# Power.net
KiCad netlist of a schematic drawn in Altium Designer
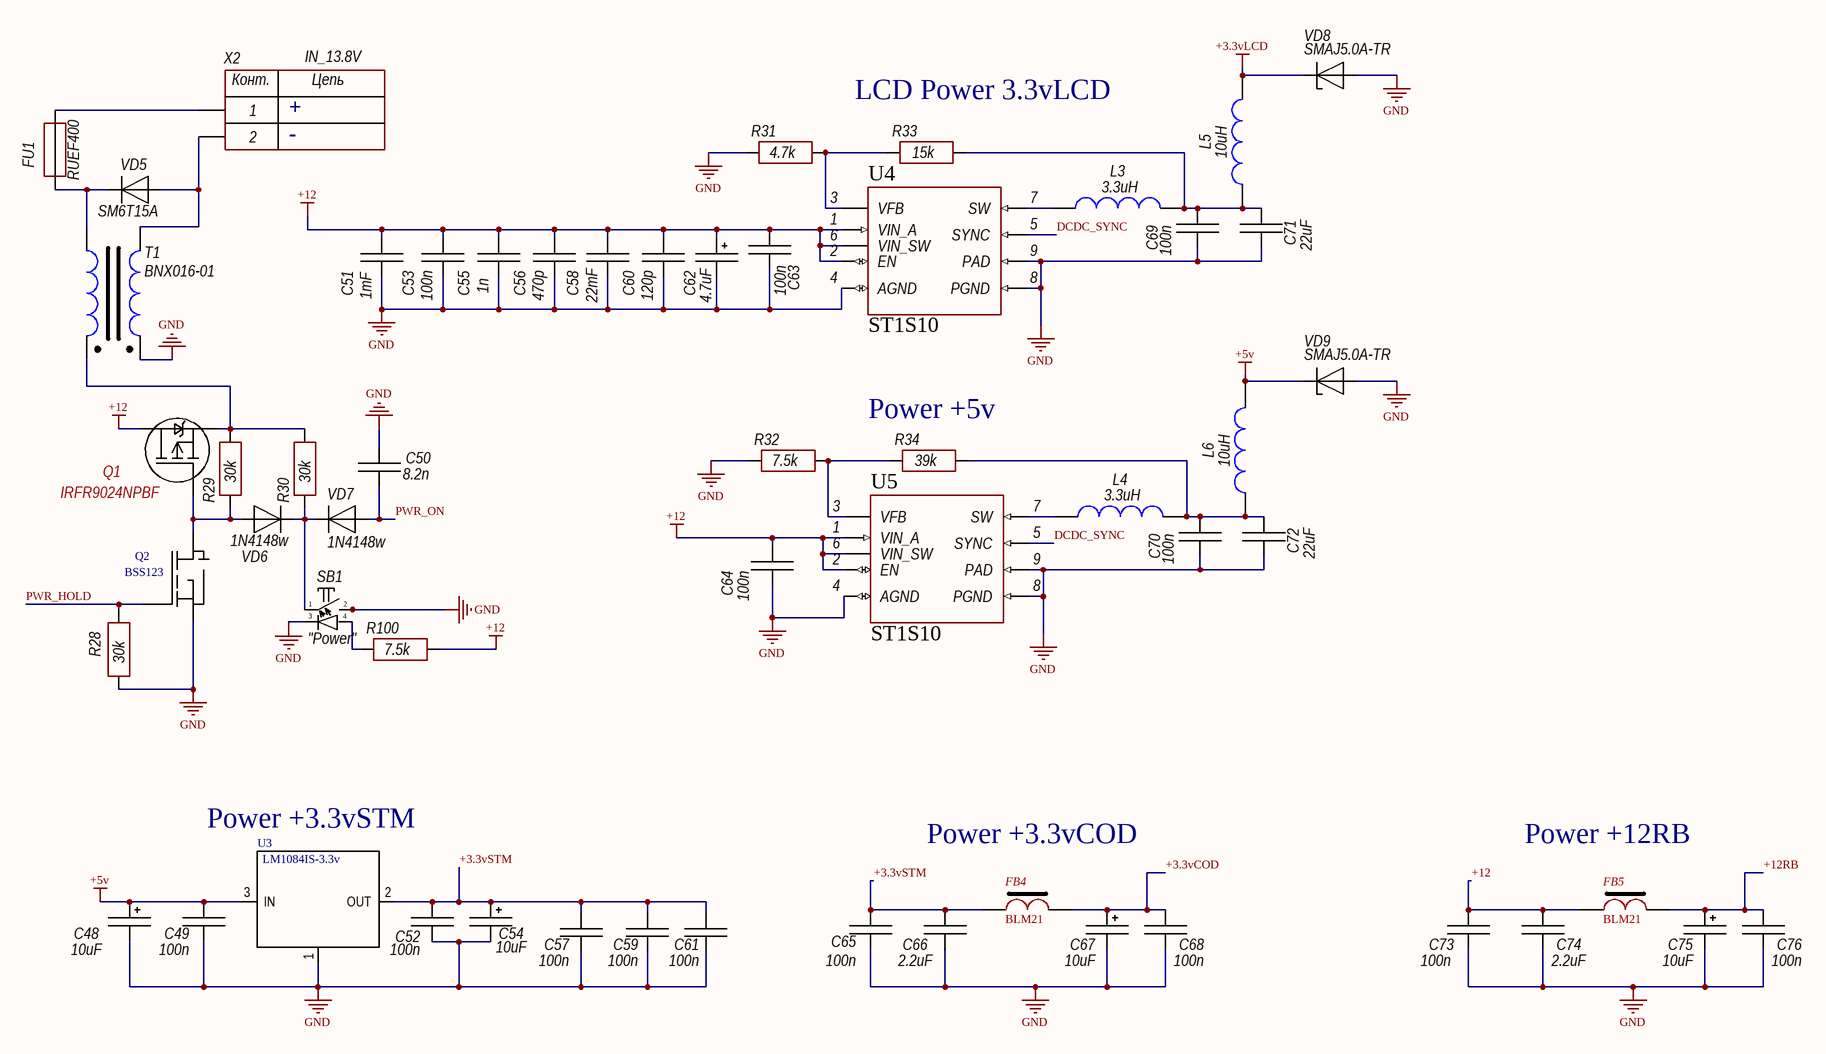
[diagram p0: Power.SchDoc]

(export (version "E")
  (design (tool "Eeschema 10.0.6"))
  (components
    (comp (ref "C48")
      (value "10uF")
      (footprint "standard:TANTAL_B")
      (libsource (lib "Discrete") (part "TantalCap"))
    )
    (comp (ref "C49")
      (value "100n")
      (footprint "standard:CH0805C")
      (libsource (lib "Discrete") (part "Capacitor"))
    )
    (comp (ref "C50")
      (value "8.2n")
      (footprint "standard:CH0805C")
      (libsource (lib "Discrete") (part "Capacitor"))
    )
    (comp (ref "C51")
      (value "1mF")
      (footprint "standard:CH0805C")
      (libsource (lib "Discrete") (part "Capacitor"))
    )
    (comp (ref "C52")
      (value "100n")
      (footprint "standard:CH0805C")
      (libsource (lib "Discrete") (part "Capacitor"))
    )
    (comp (ref "C53")
      (value "100n")
      (footprint "standard:CH0805C")
      (libsource (lib "Discrete") (part "Capacitor"))
    )
    (comp (ref "C54")
      (value "10uF")
      (footprint "standard:TANTAL_B")
      (libsource (lib "Discrete") (part "TantalCap"))
    )
    (comp (ref "C55")
      (value "1n")
      (footprint "standard:CH0805C")
      (libsource (lib "Discrete") (part "Capacitor"))
    )
    (comp (ref "C56")
      (value "470p")
      (footprint "standard:CH0805C")
      (libsource (lib "Discrete") (part "Capacitor"))
    )
    (comp (ref "C57")
      (value "100n")
      (footprint "standard:CH0805C")
      (libsource (lib "Discrete") (part "Capacitor"))
    )
    (comp (ref "C58")
      (value "22mF")
      (footprint "standard:CH1210C")
      (libsource (lib "Discrete") (part "Capacitor"))
    )
    (comp (ref "C59")
      (value "100n")
      (footprint "standard:CH0805C")
      (libsource (lib "Discrete") (part "Capacitor"))
    )
    (comp (ref "C60")
      (value "120p")
      (footprint "standard:CH0805C")
      (libsource (lib "Discrete") (part "Capacitor"))
    )
    (comp (ref "C61")
      (value "100n")
      (footprint "standard:CH0805C")
      (libsource (lib "Discrete") (part "Capacitor"))
    )
    (comp (ref "C62")
      (value "4.7uF")
      (footprint "standard:D6.3C2.5H11")
      (libsource (lib "Discrete") (part "AlumCap"))
    )
    (comp (ref "C63")
      (value "100n")
      (footprint "standard:CH0805C")
      (libsource (lib "Discrete") (part "Capacitor"))
    )
    (comp (ref "C64")
      (value "100n")
      (footprint "standard:CH0805C")
      (libsource (lib "Discrete") (part "Capacitor"))
    )
    (comp (ref "C65")
      (value "100n")
      (footprint "standard:CH0805C")
      (libsource (lib "Discrete") (part "Capacitor"))
    )
    (comp (ref "C66")
      (value "2.2uF")
      (footprint "standard:CH0805C")
      (libsource (lib "Discrete") (part "Capacitor"))
    )
    (comp (ref "C67")
      (value "10uF")
      (footprint "standard:TANTAL_B")
      (libsource (lib "Discrete") (part "TantalCap"))
    )
    (comp (ref "C68")
      (value "100n")
      (footprint "standard:CH0805C")
      (libsource (lib "Discrete") (part "Capacitor"))
    )
    (comp (ref "C69")
      (value "100n")
      (footprint "standard:CH0805C")
      (libsource (lib "Discrete") (part "Capacitor"))
    )
    (comp (ref "C70")
      (value "100n")
      (footprint "standard:CH0805C")
      (libsource (lib "Discrete") (part "Capacitor"))
    )
    (comp (ref "C71")
      (value "22uF")
      (footprint "standard:CH1210C")
      (libsource (lib "Discrete") (part "Capacitor"))
    )
    (comp (ref "C72")
      (value "22uF")
      (footprint "standard:CH1210C")
      (libsource (lib "Discrete") (part "Capacitor"))
    )
    (comp (ref "C73")
      (value "100n")
      (footprint "standard:CH0805C")
      (libsource (lib "Discrete") (part "Capacitor"))
    )
    (comp (ref "C74")
      (value "2.2uF")
      (footprint "standard:CH0805C")
      (libsource (lib "Discrete") (part "Capacitor"))
    )
    (comp (ref "C75")
      (value "10uF")
      (footprint "standard:TANTAL_B")
      (libsource (lib "Discrete") (part "TantalCap"))
    )
    (comp (ref "C76")
      (value "100n")
      (footprint "standard:CH0805C")
      (libsource (lib "Discrete") (part "Capacitor"))
    )
    (comp (ref "FB4") (value "BLM21") (footprint "CH0805L") (libsource (lib "Discrete") (part "FB-1")))
    (comp (ref "FB5") (value "BLM21") (footprint "CH0805L") (libsource (lib "Discrete") (part "FB-1")))
    (comp (ref "FU1")
      (value "RUEF400")
      (footprint "Fuse: Ruef400")
      (libsource (lib "Discrete") (part "Fuse"))
    )
    (comp (ref "L3")
      (value "3.3uH")
      (footprint "custom:IND: CDRH74")
      (libsource (lib "Discrete") (part "Inductor"))
    )
    (comp (ref "L4")
      (value "3.3uH")
      (footprint "custom:IND: CDRH127")
      (libsource (lib "Discrete") (part "Inductor"))
    )
    (comp (ref "L5")
      (value "10uH")
      (footprint "custom:IND: CDRH74")
      (libsource (lib "Discrete") (part "Inductor"))
    )
    (comp (ref "L6")
      (value "10uH")
      (footprint "custom:IND: CDRH74")
      (libsource (lib "Discrete") (part "Inductor"))
    )
    (comp (ref "Q1")
      (value "IRFR9024NPBF")
      (footprint "D2PAK_132")
      (libsource (lib "Transistor") (part "P-KANAL"))
    )
    (comp (ref "Q2") (value "BSS123") (footprint "SOT23_132") (libsource (lib "Transistor") (part "BSS123")))
    (comp (ref "R28") (value "30k") (footprint "standard:CH0805R") (libsource (lib "") (part "Resistor_1")))
    (comp (ref "R29") (value "30k") (footprint "standard:CH0805R") (libsource (lib "") (part "Resistor_1")))
    (comp (ref "R30") (value "30k") (footprint "standard:CH0805R") (libsource (lib "") (part "Resistor_1")))
    (comp (ref "R31")
      (value "4.7k")
      (footprint "standard:CH0805R")
      (libsource (lib "Discrete") (part "Resistor"))
    )
    (comp (ref "R32")
      (value "7.5k")
      (footprint "standard:CH0805R")
      (libsource (lib "Discrete") (part "Resistor"))
    )
    (comp (ref "R33")
      (value "15k")
      (footprint "standard:CH0805R")
      (libsource (lib "Discrete") (part "Resistor"))
    )
    (comp (ref "R34")
      (value "39k")
      (footprint "standard:CH0805R")
      (libsource (lib "Discrete") (part "Resistor"))
    )
    (comp (ref "R100")
      (value "7.5k")
      (footprint "standard:CH0805R")
      (libsource (lib "Discrete") (part "Resistor"))
    )
    (comp (ref "SB1")
      (value "\"Power\"")
      (footprint "BUT: 6x6 LED")
      (description "6x6 mm")
      (libsource (lib "Connectors") (part "Tactile switches_LED"))
    )
    (comp (ref "T1")
      (value "BNX016-01")
      (footprint "BNX016-01")
      (fields (field (name "MANUFACTURER") "Murata Electronics North America"))
      (libsource (lib "Transformers") (part "EMI bead"))
    )
    (comp (ref "U3")
      (value "LM1084IS-3.3v")
      (footprint "TO-263-3(123)")
      (libsource (lib "Power Supplies") (part "LM1084"))
    )
    (comp (ref "U4") (value "ST1S10") (footprint "8-SOIC (PAD)") (libsource (lib "Digital") (part "ST1S10")))
    (comp (ref "U5") (value "ST1S10") (footprint "8-SOIC (PAD)") (libsource (lib "Digital") (part "ST1S10")))
    (comp (ref "VD5") (value "SM6T15A") (footprint "standard:SMB") (libsource (lib "Diods") (part "Diod")))
    (comp (ref "VD6")
      (value "1N4148w")
      (footprint "standard:SOD123F")
      (libsource (lib "Diods") (part "Diod"))
    )
    (comp (ref "VD7")
      (value "1N4148w")
      (footprint "standard:SOD123F")
      (libsource (lib "Diods") (part "Diod"))
    )
    (comp (ref "VD8")
      (value "SMAJ5.0A-TR")
      (footprint "standard:SMA")
      (libsource (lib "") (part "Diod Zener_1"))
    )
    (comp (ref "VD9")
      (value "SMAJ5.0A-TR")
      (footprint "standard:SMA")
      (libsource (lib "Diods") (part "Diod Zener"))
    )
    (comp (ref "X2")
      (value "IN_13.8V")
      (footprint "custom:CON: WF-02")
      (libsource (lib "Connectors") (part "2-Connector"))
    )
  )
  (nets
    (net (code "1") (name "+3.3vLCD") (class "Default")
      (node (ref "L5") (pin "1") (pinfunction "1_1") (pintype "passive"))
      (node (ref "VD8") (pin "2") (pinfunction "C_2") (pintype "passive"))
    )
    (net (code "2") (name "+5v") (class "Default")
      (node (ref "C48") (pin "1") (pinfunction "1_1") (pintype "power_in"))
      (node (ref "C49") (pin "2") (pinfunction "2_2") (pintype "power_in"))
      (node (ref "L6") (pin "1") (pinfunction "1_1") (pintype "passive"))
      (node (ref "U3") (pin "3") (pinfunction "IN_3") (pintype "passive"))
      (node (ref "VD9") (pin "2") (pinfunction "C_2") (pintype "passive"))
    )
    (net (code "3") (name "+12") (class "Default")
      (node (ref "C51") (pin "2") (pinfunction "2_2") (pintype "power_in"))
      (node (ref "C53") (pin "2") (pinfunction "2_2") (pintype "power_in"))
      (node (ref "C55") (pin "2") (pinfunction "2_2") (pintype "power_in"))
      (node (ref "C56") (pin "2") (pinfunction "2_2") (pintype "power_in"))
      (node (ref "C58") (pin "2") (pinfunction "2_2") (pintype "power_in"))
      (node (ref "C60") (pin "2") (pinfunction "2_2") (pintype "power_in"))
      (node (ref "C62") (pin "1") (pinfunction "1_1") (pintype "power_in"))
      (node (ref "C63") (pin "2") (pinfunction "2_2") (pintype "power_in"))
      (node (ref "C64") (pin "2") (pinfunction "2_2") (pintype "power_in"))
      (node (ref "C73") (pin "2") (pinfunction "2_2") (pintype "power_in"))
      (node (ref "C74") (pin "2") (pinfunction "2_2") (pintype "power_in"))
      (node (ref "FB5") (pin "2") (pinfunction "2_2") (pintype "passive"))
      (node (ref "Q1") (pin "3") (pinfunction "Сток(Drain)_3") (pintype "passive"))
      (node (ref "R100") (pin "2") (pinfunction "2_2") (pintype "passive"))
      (node (ref "U4") (pin "1") (pinfunction "VIN_A_1") (pintype "input"))
      (node (ref "U4") (pin "2") (pinfunction "EN_2") (pintype "bidirectional"))
      (node (ref "U4") (pin "6") (pinfunction "VIN_SW_6") (pintype "power_in"))
      (node (ref "U5") (pin "1") (pinfunction "VIN_A_1") (pintype "input"))
      (node (ref "U5") (pin "2") (pinfunction "EN_2") (pintype "bidirectional"))
      (node (ref "U5") (pin "6") (pinfunction "VIN_SW_6") (pintype "power_in"))
    )
    (net (code "4") (name "/+3.3vCOD") (class "Default")
      (node (ref "C67") (pin "1") (pinfunction "1_1") (pintype "power_in"))
      (node (ref "C68") (pin "2") (pinfunction "2_2") (pintype "power_in"))
      (node (ref "FB4") (pin "1") (pinfunction "1_1") (pintype "passive"))
    )
    (net (code "5") (name "/+3.3vSTM") (class "Default")
      (node (ref "C52") (pin "2") (pinfunction "2_2") (pintype "power_in"))
      (node (ref "C54") (pin "1") (pinfunction "1_1") (pintype "power_in"))
      (node (ref "C57") (pin "2") (pinfunction "2_2") (pintype "power_in"))
      (node (ref "C59") (pin "2") (pinfunction "2_2") (pintype "power_in"))
      (node (ref "C61") (pin "2") (pinfunction "2_2") (pintype "power_in"))
      (node (ref "C65") (pin "2") (pinfunction "2_2") (pintype "power_in"))
      (node (ref "C66") (pin "2") (pinfunction "2_2") (pintype "power_in"))
      (node (ref "FB4") (pin "2") (pinfunction "2_2") (pintype "passive"))
      (node (ref "U3") (pin "2") (pinfunction "OUT_2") (pintype "passive"))
    )
    (net (code "6") (name "/+12RB") (class "Default")
      (node (ref "C75") (pin "1") (pinfunction "1_1") (pintype "power_in"))
      (node (ref "C76") (pin "2") (pinfunction "2_2") (pintype "power_in"))
      (node (ref "FB5") (pin "1") (pinfunction "1_1") (pintype "passive"))
    )
    (net (code "7") (name "/DCDC_SYNC") (class "Default")
      (node (ref "U4") (pin "5") (pinfunction "SYNC_5") (pintype "input"))
      (node (ref "U5") (pin "5") (pinfunction "SYNC_5") (pintype "input"))
    )
    (net (code "8") (name "/PWR_HOLD") (class "Default")
      (node (ref "Q2") (pin "1") (pinfunction "G_1") (pintype "passive"))
      (node (ref "R28") (pin "2") (pinfunction "2_2") (pintype "passive"))
    )
    (net (code "9") (name "/PWR_ON") (class "Default")
      (node (ref "C50") (pin "1") (pinfunction "1_1") (pintype "power_in"))
      (node (ref "VD7") (pin "1") (pinfunction "1_1") (pintype "passive"))
    )
    (net (code "10") (name "GND") (class "Default")
      (node (ref "C48") (pin "2") (pinfunction "2_2") (pintype "power_in"))
      (node (ref "C49") (pin "1") (pinfunction "1_1") (pintype "power_in"))
      (node (ref "C50") (pin "2") (pinfunction "2_2") (pintype "power_in"))
      (node (ref "C51") (pin "1") (pinfunction "1_1") (pintype "power_in"))
      (node (ref "C52") (pin "1") (pinfunction "1_1") (pintype "power_in"))
      (node (ref "C53") (pin "1") (pinfunction "1_1") (pintype "power_in"))
      (node (ref "C54") (pin "2") (pinfunction "2_2") (pintype "power_in"))
      (node (ref "C55") (pin "1") (pinfunction "1_1") (pintype "power_in"))
      (node (ref "C56") (pin "1") (pinfunction "1_1") (pintype "power_in"))
      (node (ref "C57") (pin "1") (pinfunction "1_1") (pintype "power_in"))
      (node (ref "C58") (pin "1") (pinfunction "1_1") (pintype "power_in"))
      (node (ref "C59") (pin "1") (pinfunction "1_1") (pintype "power_in"))
      (node (ref "C60") (pin "1") (pinfunction "1_1") (pintype "power_in"))
      (node (ref "C61") (pin "1") (pinfunction "1_1") (pintype "power_in"))
      (node (ref "C62") (pin "2") (pinfunction "2_2") (pintype "power_in"))
      (node (ref "C63") (pin "1") (pinfunction "1_1") (pintype "power_in"))
      (node (ref "C64") (pin "1") (pinfunction "1_1") (pintype "power_in"))
      (node (ref "C65") (pin "1") (pinfunction "1_1") (pintype "power_in"))
      (node (ref "C66") (pin "1") (pinfunction "1_1") (pintype "power_in"))
      (node (ref "C67") (pin "2") (pinfunction "2_2") (pintype "power_in"))
      (node (ref "C68") (pin "1") (pinfunction "1_1") (pintype "power_in"))
      (node (ref "C69") (pin "1") (pinfunction "1_1") (pintype "power_in"))
      (node (ref "C70") (pin "1") (pinfunction "1_1") (pintype "power_in"))
      (node (ref "C71") (pin "1") (pinfunction "1_1") (pintype "power_in"))
      (node (ref "C72") (pin "1") (pinfunction "1_1") (pintype "power_in"))
      (node (ref "C73") (pin "1") (pinfunction "1_1") (pintype "power_in"))
      (node (ref "C74") (pin "1") (pinfunction "1_1") (pintype "power_in"))
      (node (ref "C75") (pin "2") (pinfunction "2_2") (pintype "power_in"))
      (node (ref "C76") (pin "1") (pinfunction "1_1") (pintype "power_in"))
      (node (ref "Q2") (pin "2") (pinfunction "S_2") (pintype "passive"))
      (node (ref "R28") (pin "1") (pinfunction "1_1") (pintype "passive"))
      (node (ref "R31") (pin "1") (pinfunction "1_1") (pintype "passive"))
      (node (ref "R32") (pin "1") (pinfunction "1_1") (pintype "passive"))
      (node (ref "SB1") (pin "2") (pinfunction "2_2") (pintype "passive"))
      (node (ref "SB1") (pin "3") (pinfunction "3_3") (pintype "passive"))
      (node (ref "T1") (pin "3") (pinfunction "3_3") (pintype "passive"))
      (node (ref "U3") (pin "1") (pintype "passive"))
      (node (ref "U4") (pin "4") (pinfunction "AGND_4") (pintype "bidirectional"))
      (node (ref "U4") (pin "8") (pinfunction "PGND_8") (pintype "input"))
      (node (ref "U4") (pin "9") (pinfunction "PAD_9") (pintype "input"))
      (node (ref "U5") (pin "4") (pinfunction "AGND_4") (pintype "bidirectional"))
      (node (ref "U5") (pin "8") (pinfunction "PGND_8") (pintype "input"))
      (node (ref "U5") (pin "9") (pinfunction "PAD_9") (pintype "input"))
      (node (ref "VD8") (pin "1") (pinfunction "A_1") (pintype "passive"))
      (node (ref "VD9") (pin "1") (pinfunction "A_1") (pintype "passive"))
    )
    (net (code "11") (name "Net-(C69-Pad2)") (class "Default")
      (node (ref "C69") (pin "2") (pinfunction "2_2") (pintype "power_in"))
      (node (ref "C71") (pin "2") (pinfunction "2_2") (pintype "power_in"))
      (node (ref "L3") (pin "1") (pinfunction "1_1") (pintype "passive"))
      (node (ref "L5") (pin "2") (pinfunction "2_2") (pintype "passive"))
      (node (ref "R33") (pin "2") (pinfunction "2_2") (pintype "passive"))
    )
    (net (code "12") (name "Net-(C70-Pad2)") (class "Default")
      (node (ref "C70") (pin "2") (pinfunction "2_2") (pintype "power_in"))
      (node (ref "C72") (pin "2") (pinfunction "2_2") (pintype "power_in"))
      (node (ref "L4") (pin "1") (pinfunction "1_1") (pintype "passive"))
      (node (ref "L6") (pin "2") (pinfunction "2_2") (pintype "passive"))
      (node (ref "R34") (pin "2") (pinfunction "2_2") (pintype "passive"))
    )
    (net (code "13") (name "Net-(FU1-Pad1)") (class "Default")
      (node (ref "FU1") (pin "1") (pinfunction "1_1") (pintype "passive"))
      (node (ref "T1") (pin "2") (pinfunction "2_2") (pintype "passive"))
      (node (ref "VD5") (pin "2") (pinfunction "2_2") (pintype "passive"))
    )
    (net (code "14") (name "Net-(FU1-Pad2)") (class "Default")
      (node (ref "FU1") (pin "2") (pinfunction "2_2") (pintype "passive"))
      (node (ref "X2") (pin "1") (pinfunction "1_1") (pintype "passive"))
    )
    (net (code "15") (name "Net-(Q1-I)") (class "Default")
      (node (ref "Q1") (pin "2") (pinfunction "I_2") (pintype "passive"))
      (node (ref "R29") (pin "2") (pinfunction "2_2") (pintype "passive"))
      (node (ref "R30") (pin "2") (pinfunction "2_2") (pintype "passive"))
      (node (ref "T1") (pin "1") (pinfunction "1_1") (pintype "passive"))
    )
    (net (code "16") (name "Net-(Q1-Затвор(Gate))") (class "Default")
      (node (ref "Q1") (pin "1") (pinfunction "Затвор(Gate)_1") (pintype "passive"))
      (node (ref "Q2") (pin "3") (pinfunction "D_3") (pintype "passive"))
      (node (ref "R29") (pin "1") (pinfunction "1_1") (pintype "passive"))
      (node (ref "VD6") (pin "1") (pinfunction "1_1") (pintype "passive"))
    )
    (net (code "17") (name "Net-(R30-Pad1)") (class "Default")
      (node (ref "R30") (pin "1") (pinfunction "1_1") (pintype "passive"))
      (node (ref "SB1") (pin "1") (pinfunction "1_1") (pintype "passive"))
      (node (ref "VD6") (pin "2") (pinfunction "2_2") (pintype "passive"))
      (node (ref "VD7") (pin "2") (pinfunction "2_2") (pintype "passive"))
    )
    (net (code "18") (name "Net-(R100-Pad1)") (class "Default")
      (node (ref "R100") (pin "1") (pinfunction "1_1") (pintype "passive"))
      (node (ref "SB1") (pin "4") (pinfunction "4_4") (pintype "passive"))
    )
    (net (code "19") (name "Net-(T1-Pad4)") (class "Default")
      (node (ref "T1") (pin "4") (pinfunction "4_4") (pintype "passive"))
      (node (ref "VD5") (pin "1") (pinfunction "1_1") (pintype "passive"))
      (node (ref "X2") (pin "2") (pinfunction "2_2") (pintype "passive"))
    )
    (net (code "20") (name "Net-(U4-SW)") (class "Default")
      (node (ref "L3") (pin "2") (pinfunction "2_2") (pintype "passive"))
      (node (ref "U4") (pin "7") (pinfunction "SW_7") (pintype "input"))
    )
    (net (code "21") (name "Net-(U4-VFB)") (class "Default")
      (node (ref "R31") (pin "2") (pinfunction "2_2") (pintype "passive"))
      (node (ref "R33") (pin "1") (pinfunction "1_1") (pintype "passive"))
      (node (ref "U4") (pin "3") (pinfunction "VFB_3") (pintype "power_in"))
    )
    (net (code "22") (name "Net-(U5-SW)") (class "Default")
      (node (ref "L4") (pin "2") (pinfunction "2_2") (pintype "passive"))
      (node (ref "U5") (pin "7") (pinfunction "SW_7") (pintype "input"))
    )
    (net (code "23") (name "Net-(U5-VFB)") (class "Default")
      (node (ref "R32") (pin "2") (pinfunction "2_2") (pintype "passive"))
      (node (ref "R34") (pin "1") (pinfunction "1_1") (pintype "passive"))
      (node (ref "U5") (pin "3") (pinfunction "VFB_3") (pintype "power_in"))
    )
  )
)
